# FAT42.net
KiCad netlist of a schematic drawn in Altium Designer
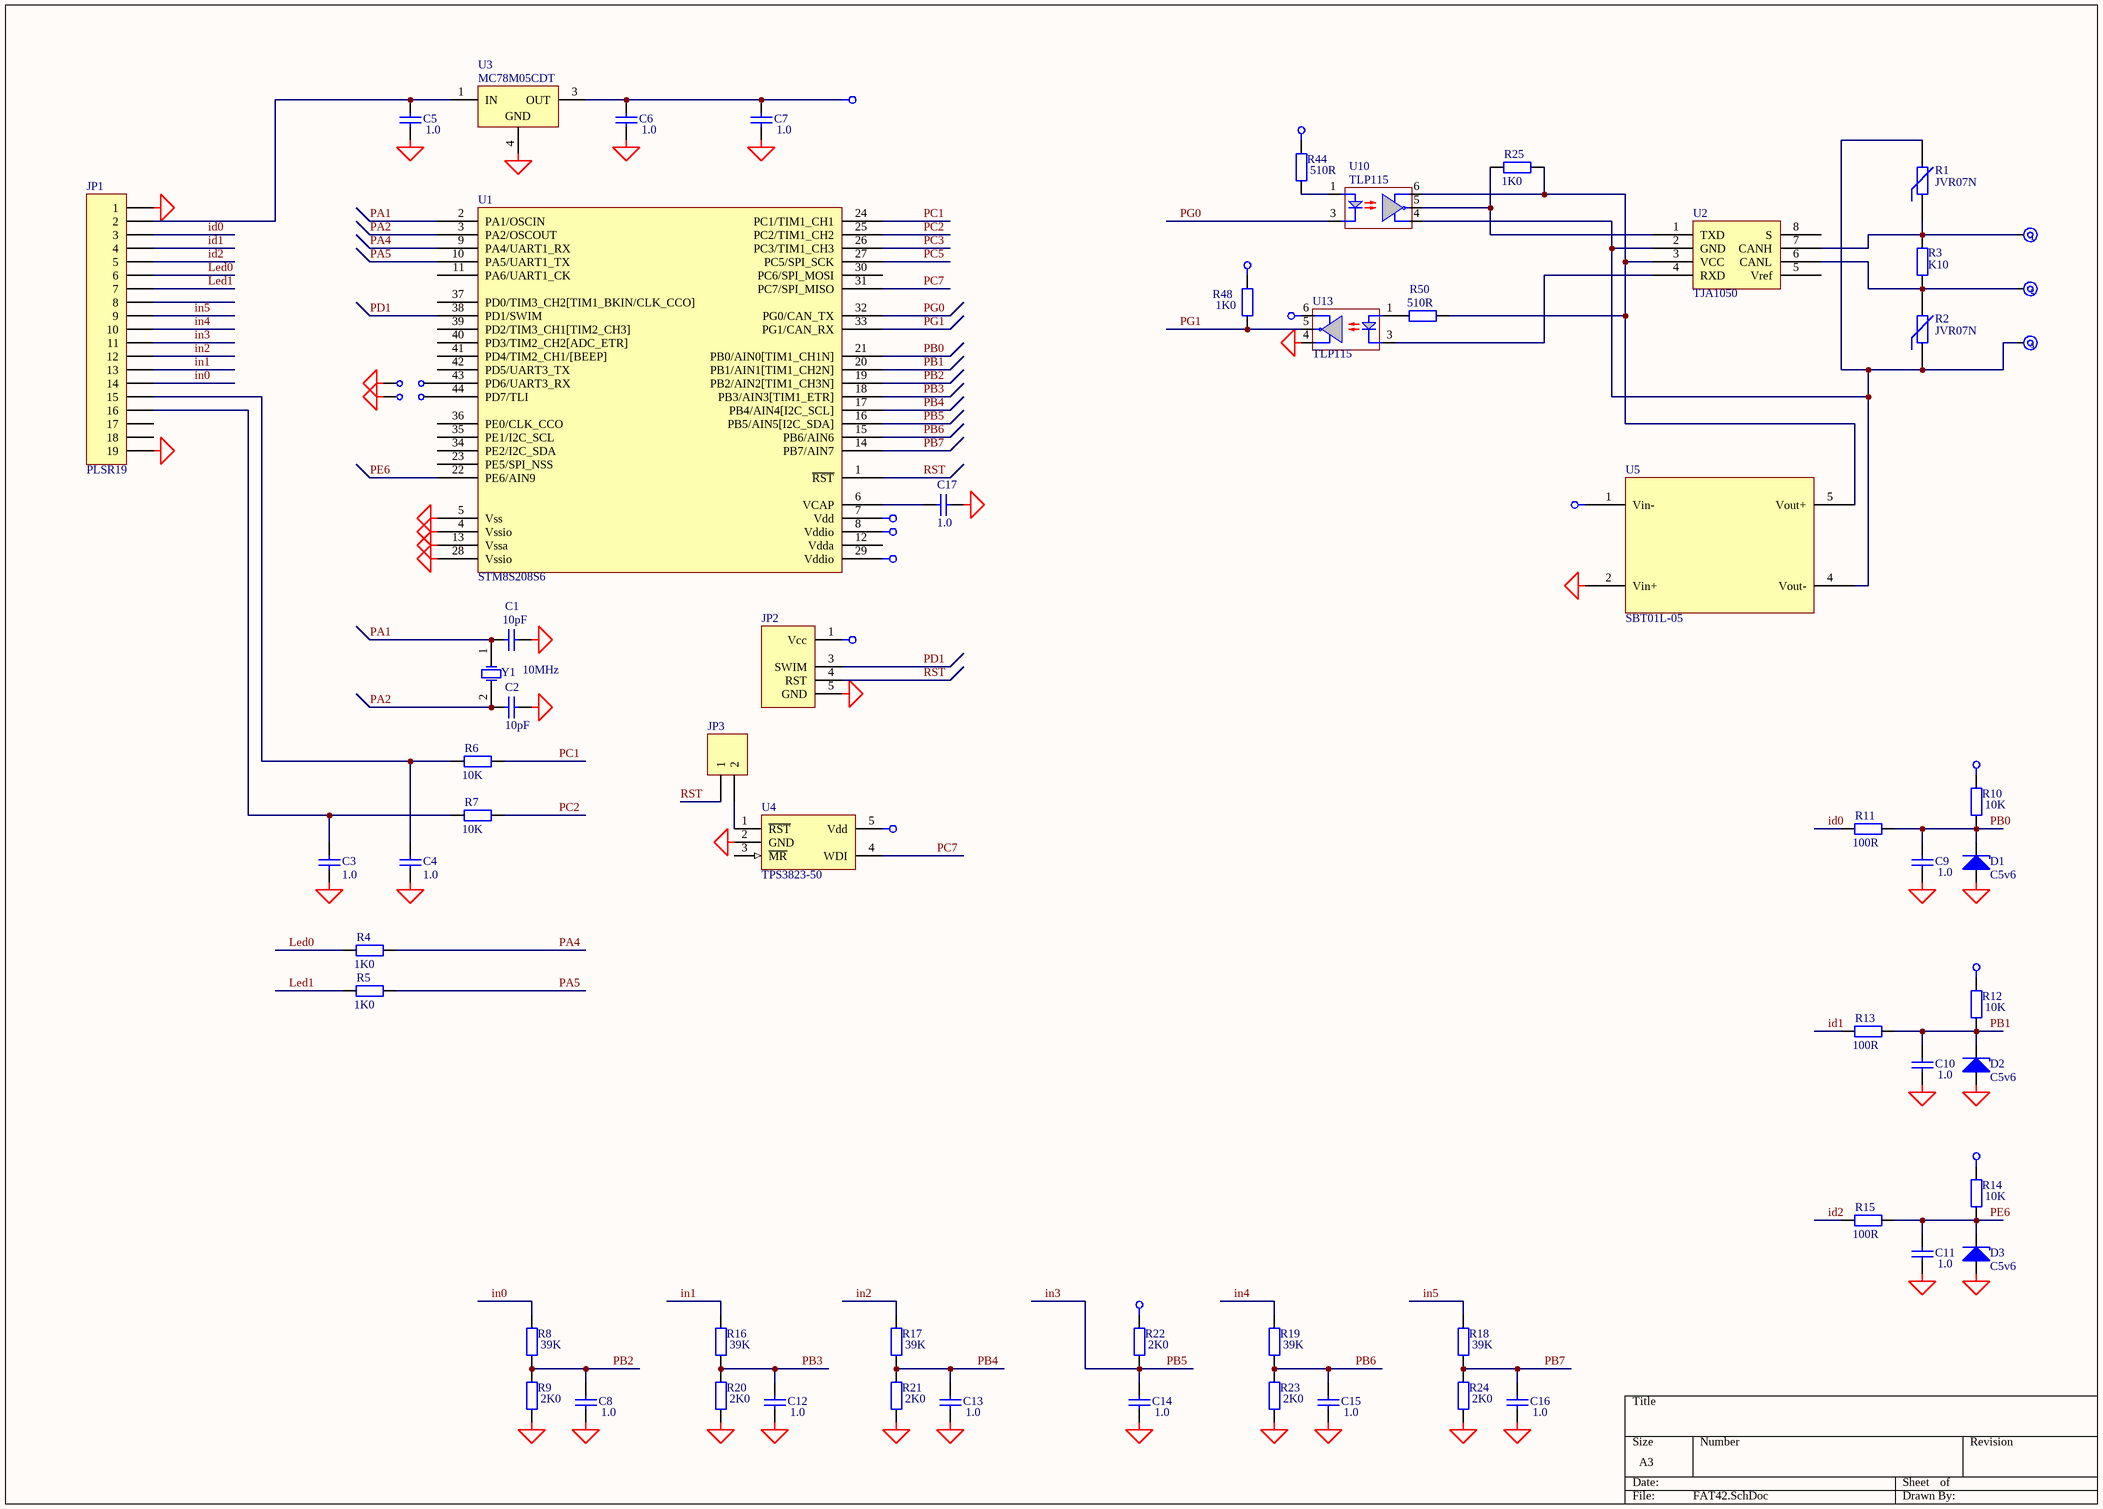
[diagram p0: FAT42.SchDoc]

(export (version "E")
  (design (tool "Eeschema 10.0.6"))
  (components
    (comp (ref "1")
      (value "~")
      (footprint "PIN2R")
      (description "Socket")
      (fields (field (name "MANUFACTURER") "Generic Components") (field (name "PUBLISHER") "Altium Limited"))
      (libsource (lib "PAL") (part "Socket_Ring"))
    )
    (comp (ref "2")
      (value "~")
      (footprint "PIN2R")
      (description "Socket")
      (fields (field (name "MANUFACTURER") "Generic Components") (field (name "PUBLISHER") "Altium Limited"))
      (libsource (lib "PAL") (part "Socket_Ring"))
    )
    (comp (ref "3")
      (value "~")
      (footprint "PIN2R")
      (description "Socket")
      (fields (field (name "MANUFACTURER") "Generic Components") (field (name "PUBLISHER") "Altium Limited"))
      (libsource (lib "PAL") (part "Socket_Ring"))
    )
    (comp (ref "C1")
      (value "10pF")
      (footprint "_1206")
      (description "Capacitor (Semiconductor SIM Model)")
      (fields (field (name "MANUFACTURER") "Generic Components") (field (name "PUBLISHER") "Altium Limited"))
      (libsource (lib "Miscellaneous Devices") (part "Cap Semi"))
    )
    (comp (ref "C2")
      (value "10pF")
      (footprint "_1206")
      (description "Capacitor (Semiconductor SIM Model)")
      (fields (field (name "MANUFACTURER") "Generic Components") (field (name "PUBLISHER") "Altium Limited"))
      (libsource (lib "Miscellaneous Devices") (part "Cap Semi"))
    )
    (comp (ref "C3")
      (value "1.0")
      (footprint "_1206")
      (description "Capacitor (Semiconductor SIM Model)")
      (fields (field (name "MANUFACTURER") "Generic Components") (field (name "PUBLISHER") "Altium Limited"))
      (libsource (lib "Miscellaneous Devices") (part "Cap Semi"))
    )
    (comp (ref "C4")
      (value "1.0")
      (footprint "_1206")
      (description "Capacitor (Semiconductor SIM Model)")
      (fields (field (name "MANUFACTURER") "Generic Components") (field (name "PUBLISHER") "Altium Limited"))
      (libsource (lib "Miscellaneous Devices") (part "Cap Semi"))
    )
    (comp (ref "C5")
      (value "1.0")
      (footprint "_1206")
      (description "Capacitor (Semiconductor SIM Model)")
      (fields (field (name "MANUFACTURER") "Generic Components") (field (name "PUBLISHER") "Altium Limited"))
      (libsource (lib "Miscellaneous Devices") (part "Cap Semi"))
    )
    (comp (ref "C6")
      (value "1.0")
      (footprint "_1206")
      (description "Capacitor (Semiconductor SIM Model)")
      (fields (field (name "MANUFACTURER") "Generic Components") (field (name "PUBLISHER") "Altium Limited"))
      (libsource (lib "Miscellaneous Devices") (part "Cap Semi"))
    )
    (comp (ref "C7")
      (value "1.0")
      (footprint "_1206")
      (description "Capacitor (Semiconductor SIM Model)")
      (fields (field (name "MANUFACTURER") "Generic Components") (field (name "PUBLISHER") "Altium Limited"))
      (libsource (lib "Miscellaneous Devices") (part "Cap Semi"))
    )
    (comp (ref "C8")
      (value "1.0")
      (footprint "_1206")
      (description "Capacitor (Semiconductor SIM Model)")
      (fields (field (name "MANUFACTURER") "Generic Components") (field (name "PUBLISHER") "Altium Limited"))
      (libsource (lib "Miscellaneous Devices") (part "Cap Semi"))
    )
    (comp (ref "C9")
      (value "1.0")
      (footprint "_1206")
      (description "Capacitor (Semiconductor SIM Model)")
      (fields (field (name "MANUFACTURER") "Generic Components") (field (name "PUBLISHER") "Altium Limited"))
      (libsource (lib "Miscellaneous Devices") (part "Cap Semi"))
    )
    (comp (ref "C10")
      (value "1.0")
      (footprint "_1206")
      (description "Capacitor (Semiconductor SIM Model)")
      (fields (field (name "MANUFACTURER") "Generic Components") (field (name "PUBLISHER") "Altium Limited"))
      (libsource (lib "Miscellaneous Devices") (part "Cap Semi"))
    )
    (comp (ref "C11")
      (value "1.0")
      (footprint "_1206")
      (description "Capacitor (Semiconductor SIM Model)")
      (fields (field (name "MANUFACTURER") "Generic Components") (field (name "PUBLISHER") "Altium Limited"))
      (libsource (lib "Miscellaneous Devices") (part "Cap Semi"))
    )
    (comp (ref "C12")
      (value "1.0")
      (footprint "_1206")
      (description "Capacitor (Semiconductor SIM Model)")
      (fields (field (name "MANUFACTURER") "Generic Components") (field (name "PUBLISHER") "Altium Limited"))
      (libsource (lib "Miscellaneous Devices") (part "Cap Semi"))
    )
    (comp (ref "C13")
      (value "1.0")
      (footprint "_1206")
      (description "Capacitor (Semiconductor SIM Model)")
      (fields (field (name "MANUFACTURER") "Generic Components") (field (name "PUBLISHER") "Altium Limited"))
      (libsource (lib "Miscellaneous Devices") (part "Cap Semi"))
    )
    (comp (ref "C14")
      (value "1.0")
      (footprint "_1206")
      (description "Capacitor (Semiconductor SIM Model)")
      (fields (field (name "MANUFACTURER") "Generic Components") (field (name "PUBLISHER") "Altium Limited"))
      (libsource (lib "Miscellaneous Devices") (part "Cap Semi"))
    )
    (comp (ref "C15")
      (value "1.0")
      (footprint "_1206")
      (description "Capacitor (Semiconductor SIM Model)")
      (fields (field (name "MANUFACTURER") "Generic Components") (field (name "PUBLISHER") "Altium Limited"))
      (libsource (lib "Miscellaneous Devices") (part "Cap Semi"))
    )
    (comp (ref "C16")
      (value "1.0")
      (footprint "_1206")
      (description "Capacitor (Semiconductor SIM Model)")
      (fields (field (name "MANUFACTURER") "Generic Components") (field (name "PUBLISHER") "Altium Limited"))
      (libsource (lib "Miscellaneous Devices") (part "Cap Semi"))
    )
    (comp (ref "C17")
      (value "1.0")
      (footprint "_1206")
      (description "Capacitor (Semiconductor SIM Model)")
      (fields (field (name "MANUFACTURER") "Generic Components") (field (name "PUBLISHER") "Altium Limited"))
      (libsource (lib "Miscellaneous Devices") (part "Cap Semi"))
    )
    (comp (ref "D1")
      (value "C5v6")
      (footprint "_1206d")
      (description "Default Diode")
      (fields (field (name "MANUFACTURER") "Generic Components") (field (name "PUBLISHER") "Altium Limited"))
      (libsource (lib "PAL") (part "Zener"))
    )
    (comp (ref "D2")
      (value "C5v6")
      (footprint "_1206d")
      (description "Default Diode")
      (fields (field (name "MANUFACTURER") "Generic Components") (field (name "PUBLISHER") "Altium Limited"))
      (libsource (lib "PAL") (part "Zener"))
    )
    (comp (ref "D3")
      (value "C5v6")
      (footprint "_1206d")
      (description "Default Diode")
      (fields (field (name "MANUFACTURER") "Generic Components") (field (name "PUBLISHER") "Altium Limited"))
      (libsource (lib "PAL") (part "Zener"))
    )
    (comp (ref "J1")
      (value "~")
      (footprint "jmp")
      (description "Switch")
      (fields (field (name "MANUFACTURER") "Generic Components") (field (name "PUBLISHER") "Altium Limited"))
      (libsource (lib "PAL") (part "JMP"))
    )
    (comp (ref "J2")
      (value "~")
      (footprint "jmp")
      (description "Switch")
      (fields (field (name "MANUFACTURER") "Generic Components") (field (name "PUBLISHER") "Altium Limited"))
      (libsource (lib "PAL") (part "JMP"))
    )
    (comp (ref "JP1")
      (value "PLSR19")
      (footprint "HDR1X19")
      (description "Header, 19-Pin")
      (fields (field (name "MANUFACTURER") "Generic Components") (field (name "PUBLISHER") "Altium Limited"))
      (libsource (lib "Miscellaneous Connectors") (part "Header 19"))
    )
    (comp (ref "JP2") (value "~") (footprint "HDR1X5_uart") (libsource (lib "PAL") (part "SWIM_CONN")))
    (comp (ref "JP3")
      (value "PLS2")
      (footprint "HDR1X2")
      (description "Header, 2-Pin")
      (fields (field (name "MANUFACTURER") "Generic Components") (field (name "PUBLISHER") "Altium Limited"))
      (libsource (lib "Miscellaneous Connectors") (part "Header 2"))
    )
    (comp (ref "R1")
      (value "JVR07N")
      (footprint "JVR07N")
      (description "Varistor (Voltage-Sensitive Resistor)")
      (fields (field (name "MANUFACTURER") "Generic Components") (field (name "PUBLISHER") "Altium Limited"))
      (libsource (lib "Miscellaneous Devices") (part "Res Varistor"))
    )
    (comp (ref "R2")
      (value "JVR07N")
      (footprint "JVR07N")
      (description "Varistor (Voltage-Sensitive Resistor)")
      (fields (field (name "MANUFACTURER") "Generic Components") (field (name "PUBLISHER") "Altium Limited"))
      (libsource (lib "Miscellaneous Devices") (part "Res Varistor"))
    )
    (comp (ref "R3")
      (value "K10")
      (footprint "_1206")
      (description "Resistor")
      (fields (field (name "MANUFACTURER") "Generic Components") (field (name "PUBLISHER") "Altium Limited"))
      (libsource (lib "") (part "Res2_5"))
    )
    (comp (ref "R4")
      (value "1K0")
      (footprint "_1206")
      (description "Resistor")
      (fields (field (name "MANUFACTURER") "Generic Components") (field (name "PUBLISHER") "Altium Limited"))
      (libsource (lib "") (part "Res2_5"))
    )
    (comp (ref "R5")
      (value "1K0")
      (footprint "_1206")
      (description "Resistor")
      (fields (field (name "MANUFACTURER") "Generic Components") (field (name "PUBLISHER") "Altium Limited"))
      (libsource (lib "") (part "Res2_5"))
    )
    (comp (ref "R6")
      (value "10K")
      (footprint "_1206")
      (description "Resistor")
      (fields (field (name "MANUFACTURER") "Generic Components") (field (name "PUBLISHER") "Altium Limited"))
      (libsource (lib "") (part "Res2_2"))
    )
    (comp (ref "R7")
      (value "10K")
      (footprint "_1206")
      (description "Resistor")
      (fields (field (name "MANUFACTURER") "Generic Components") (field (name "PUBLISHER") "Altium Limited"))
      (libsource (lib "") (part "Res2_2"))
    )
    (comp (ref "R8")
      (value "39K")
      (footprint "_1206")
      (description "Resistor")
      (fields (field (name "MANUFACTURER") "Generic Components") (field (name "PUBLISHER") "Altium Limited"))
      (libsource (lib "Miscellaneous Devices") (part "Res2"))
    )
    (comp (ref "R9")
      (value "2K0")
      (footprint "_1206")
      (description "Resistor")
      (fields (field (name "MANUFACTURER") "Generic Components") (field (name "PUBLISHER") "Altium Limited"))
      (libsource (lib "Miscellaneous Devices") (part "Res2"))
    )
    (comp (ref "R10")
      (value "10K")
      (footprint "_1206")
      (description "Resistor")
      (fields (field (name "MANUFACTURER") "Generic Components") (field (name "PUBLISHER") "Altium Limited"))
      (libsource (lib "") (part "Res2_3"))
    )
    (comp (ref "R11")
      (value "100R")
      (footprint "_1206")
      (description "Resistor")
      (fields (field (name "MANUFACTURER") "Generic Components") (field (name "PUBLISHER") "Altium Limited"))
      (libsource (lib "") (part "Res2_2"))
    )
    (comp (ref "R12")
      (value "10K")
      (footprint "_1206")
      (description "Resistor")
      (fields (field (name "MANUFACTURER") "Generic Components") (field (name "PUBLISHER") "Altium Limited"))
      (libsource (lib "") (part "Res2_3"))
    )
    (comp (ref "R13")
      (value "100R")
      (footprint "_1206")
      (description "Resistor")
      (fields (field (name "MANUFACTURER") "Generic Components") (field (name "PUBLISHER") "Altium Limited"))
      (libsource (lib "") (part "Res2_2"))
    )
    (comp (ref "R14")
      (value "10K")
      (footprint "_1206")
      (description "Resistor")
      (fields (field (name "MANUFACTURER") "Generic Components") (field (name "PUBLISHER") "Altium Limited"))
      (libsource (lib "") (part "Res2_3"))
    )
    (comp (ref "R15")
      (value "100R")
      (footprint "_1206")
      (description "Resistor")
      (fields (field (name "MANUFACTURER") "Generic Components") (field (name "PUBLISHER") "Altium Limited"))
      (libsource (lib "") (part "Res2_2"))
    )
    (comp (ref "R16")
      (value "39K")
      (footprint "_1206")
      (description "Resistor")
      (fields (field (name "MANUFACTURER") "Generic Components") (field (name "PUBLISHER") "Altium Limited"))
      (libsource (lib "Miscellaneous Devices") (part "Res2"))
    )
    (comp (ref "R17")
      (value "39K")
      (footprint "_1206")
      (description "Resistor")
      (fields (field (name "MANUFACTURER") "Generic Components") (field (name "PUBLISHER") "Altium Limited"))
      (libsource (lib "Miscellaneous Devices") (part "Res2"))
    )
    (comp (ref "R18")
      (value "39K")
      (footprint "_1206")
      (description "Resistor")
      (fields (field (name "MANUFACTURER") "Generic Components") (field (name "PUBLISHER") "Altium Limited"))
      (libsource (lib "Miscellaneous Devices") (part "Res2"))
    )
    (comp (ref "R19")
      (value "39K")
      (footprint "_1206")
      (description "Resistor")
      (fields (field (name "MANUFACTURER") "Generic Components") (field (name "PUBLISHER") "Altium Limited"))
      (libsource (lib "Miscellaneous Devices") (part "Res2"))
    )
    (comp (ref "R20")
      (value "2K0")
      (footprint "_1206")
      (description "Resistor")
      (fields (field (name "MANUFACTURER") "Generic Components") (field (name "PUBLISHER") "Altium Limited"))
      (libsource (lib "Miscellaneous Devices") (part "Res2"))
    )
    (comp (ref "R21")
      (value "2K0")
      (footprint "_1206")
      (description "Resistor")
      (fields (field (name "MANUFACTURER") "Generic Components") (field (name "PUBLISHER") "Altium Limited"))
      (libsource (lib "Miscellaneous Devices") (part "Res2"))
    )
    (comp (ref "R22")
      (value "2K0")
      (footprint "_1206")
      (description "Resistor")
      (fields (field (name "MANUFACTURER") "Generic Components") (field (name "PUBLISHER") "Altium Limited"))
      (libsource (lib "Miscellaneous Devices") (part "Res2"))
    )
    (comp (ref "R23")
      (value "2K0")
      (footprint "_1206")
      (description "Resistor")
      (fields (field (name "MANUFACTURER") "Generic Components") (field (name "PUBLISHER") "Altium Limited"))
      (libsource (lib "Miscellaneous Devices") (part "Res2"))
    )
    (comp (ref "R24")
      (value "2K0")
      (footprint "_1206")
      (description "Resistor")
      (fields (field (name "MANUFACTURER") "Generic Components") (field (name "PUBLISHER") "Altium Limited"))
      (libsource (lib "Miscellaneous Devices") (part "Res2"))
    )
    (comp (ref "R25")
      (value "1K0")
      (footprint "_1206")
      (description "Resistor")
      (fields (field (name "MANUFACTURER") "Generic Components") (field (name "PUBLISHER") "Altium Limited"))
      (libsource (lib "") (part "Res2_1"))
    )
    (comp (ref "R44")
      (value "510R")
      (footprint "_1206")
      (description "Resistor")
      (fields (field (name "MANUFACTURER") "Generic Components") (field (name "PUBLISHER") "Altium Limited"))
      (libsource (lib "") (part "Res2_5"))
    )
    (comp (ref "R48")
      (value "1K0")
      (footprint "_1206")
      (description "Resistor")
      (fields (field (name "MANUFACTURER") "Generic Components") (field (name "PUBLISHER") "Altium Limited"))
      (libsource (lib "") (part "Res2_5"))
    )
    (comp (ref "R50")
      (value "510R")
      (footprint "_1206")
      (description "Resistor")
      (fields (field (name "MANUFACTURER") "Generic Components") (field (name "PUBLISHER") "Altium Limited"))
      (libsource (lib "") (part "Res2_4"))
    )
    (comp (ref "U1")
      (value "STM8S208S6")
      (footprint "QFP10X10-G44/G10N")
      (libsource (lib "PAL") (part "STM8S208S6"))
    )
    (comp (ref "U2") (value "TJA1050") (footprint "SO-G8/D5") (libsource (lib "PAL") (part "TJA1050")))
    (comp (ref "U3")
      (value "MC78M05CDT")
      (footprint "SIP-G3/Z11.05")
      (description "Three-Terminal Medium Current Positive Voltage Regulator")
      (fields (field (name "MANUFACTURER") "ON Semiconductor") (field (name "PUBLISHER") "Altium Limited"))
      (libsource (lib "ON Semi Power Mgt Voltage Regulator") (part "MC78M05CDT"))
    )
    (comp (ref "U4")
      (value "TPS3823-50")
      (footprint "SO-G5/P.95")
      (description "Reset IC")
      (fields
        (field (name "MANUFACTURER") "National Semiconductor")
        (field (name "PUBLISHER") "Altium Limited")
      )
      (libsource (lib "PAL") (part "TPS3823"))
    )
    (comp (ref "U5") (value "SBT01L-05") (footprint "SBT01DET01") (libsource (lib "PAL") (part "SBT01L")))
    (comp (ref "U10") (value "TLP115") (footprint "tlp115") (libsource (lib "PAL") (part "TLP115")))
    (comp (ref "U13") (value "TLP115") (footprint "tlp115") (libsource (lib "") (part "TLP115_1")))
    (comp (ref "Y1")
      (value "10MHz")
      (footprint "QWARZ1")
      (description "Crystal Oscillator")
      (fields (field (name "MANUFACTURER") "Generic Components") (field (name "PUBLISHER") "Altium Limited"))
      (libsource (lib "Miscellaneous Devices") (part "XTAL"))
    )
  )
  (nets
    (net (code "1") (name "+5v") (class "Default")
      (node (ref "C6") (pin "2") (pinfunction "2_2") (pintype "passive"))
      (node (ref "C7") (pin "2") (pinfunction "2_2") (pintype "passive"))
      (node (ref "JP2") (pin "1") (pinfunction "Vcc_1") (pintype "passive"))
      (node (ref "R10") (pin "1") (pinfunction "1_1") (pintype "passive"))
      (node (ref "R12") (pin "1") (pinfunction "1_1") (pintype "passive"))
      (node (ref "R14") (pin "1") (pinfunction "1_1") (pintype "passive"))
      (node (ref "R22") (pin "2") (pinfunction "2_2") (pintype "passive"))
      (node (ref "R44") (pin "2") (pinfunction "2_2") (pintype "passive"))
      (node (ref "R48") (pin "2") (pinfunction "2_2") (pintype "passive"))
      (node (ref "U1") (pin "29") (pinfunction "Vddio_29") (pintype "passive"))
      (node (ref "U1") (pin "7") (pinfunction "Vdd_7") (pintype "passive"))
      (node (ref "U1") (pin "8") (pinfunction "Vddio_8") (pintype "passive"))
      (node (ref "U13") (pin "6") (pinfunction "6_6") (pintype "passive"))
      (node (ref "U3") (pin "3") (pinfunction "OUT_3") (pintype "power_in"))
      (node (ref "U4") (pin "5") (pinfunction "Vdd_5") (pintype "power_in"))
      (node (ref "U5") (pin "1") (pinfunction "Vin-_1") (pintype "passive"))
    )
    (net (code "2") (name "/Led0") (class "Default")
      (node (ref "JP1") (pin "6") (pinfunction "6_6") (pintype "passive"))
      (node (ref "R4") (pin "1") (pinfunction "1_1") (pintype "passive"))
    )
    (net (code "3") (name "/Led1") (class "Default")
      (node (ref "JP1") (pin "7") (pinfunction "7_7") (pintype "passive"))
      (node (ref "R5") (pin "1") (pinfunction "1_1") (pintype "passive"))
    )
    (net (code "4") (name "/PA1") (class "Default")
      (node (ref "C1") (pin "2") (pinfunction "2_2") (pintype "passive"))
      (node (ref "U1") (pin "2") (pinfunction "PA1/OSCIN_2") (pintype "passive"))
      (node (ref "Y1") (pin "1") (pinfunction "OSC1_1") (pintype "passive"))
    )
    (net (code "5") (name "/PA2") (class "Default")
      (node (ref "C2") (pin "2") (pinfunction "2_2") (pintype "passive"))
      (node (ref "U1") (pin "3") (pinfunction "PA2/OSCOUT_3") (pintype "passive"))
      (node (ref "Y1") (pin "2") (pinfunction "OSC2_2") (pintype "passive"))
    )
    (net (code "6") (name "/PA4") (class "Default")
      (node (ref "R4") (pin "2") (pinfunction "2_2") (pintype "passive"))
      (node (ref "U1") (pin "9") (pinfunction "PA4/UART1_RX_9") (pintype "passive"))
    )
    (net (code "7") (name "/PA5") (class "Default")
      (node (ref "R5") (pin "2") (pinfunction "2_2") (pintype "passive"))
      (node (ref "U1") (pin "10") (pinfunction "PA5/UART1_TX_10") (pintype "passive"))
    )
    (net (code "8") (name "/PB0") (class "Default")
      (node (ref "C9") (pin "2") (pinfunction "2_2") (pintype "passive"))
      (node (ref "D1") (pin "2") (pinfunction "K_2") (pintype "passive"))
      (node (ref "R10") (pin "2") (pinfunction "2_2") (pintype "passive"))
      (node (ref "R11") (pin "1") (pinfunction "1_1") (pintype "passive"))
      (node (ref "U1") (pin "21") (pinfunction "PB0/AIN0[TIM1_CH1N]_21") (pintype "passive"))
    )
    (net (code "9") (name "/PB1") (class "Default")
      (node (ref "C10") (pin "2") (pinfunction "2_2") (pintype "passive"))
      (node (ref "D2") (pin "2") (pinfunction "K_2") (pintype "passive"))
      (node (ref "R12") (pin "2") (pinfunction "2_2") (pintype "passive"))
      (node (ref "R13") (pin "1") (pinfunction "1_1") (pintype "passive"))
      (node (ref "U1") (pin "20") (pinfunction "PB1/AIN1[TIM1_CH2N]_20") (pintype "passive"))
    )
    (net (code "10") (name "/PB2") (class "Default")
      (node (ref "C8") (pin "2") (pinfunction "2_2") (pintype "passive"))
      (node (ref "R8") (pin "1") (pinfunction "1_1") (pintype "passive"))
      (node (ref "R9") (pin "2") (pinfunction "2_2") (pintype "passive"))
      (node (ref "U1") (pin "19") (pinfunction "PB2/AIN2[TIM1_CH3N]_19") (pintype "passive"))
    )
    (net (code "11") (name "/PB3") (class "Default")
      (node (ref "C12") (pin "2") (pinfunction "2_2") (pintype "passive"))
      (node (ref "R16") (pin "1") (pinfunction "1_1") (pintype "passive"))
      (node (ref "R20") (pin "2") (pinfunction "2_2") (pintype "passive"))
      (node (ref "U1") (pin "18") (pinfunction "PB3/AIN3[TIM1_ETR]_18") (pintype "passive"))
    )
    (net (code "12") (name "/PB4") (class "Default")
      (node (ref "C13") (pin "2") (pinfunction "2_2") (pintype "passive"))
      (node (ref "R17") (pin "1") (pinfunction "1_1") (pintype "passive"))
      (node (ref "R21") (pin "2") (pinfunction "2_2") (pintype "passive"))
      (node (ref "U1") (pin "17") (pinfunction "PB4/AIN4[I2C_SCL]_17") (pintype "passive"))
    )
    (net (code "13") (name "/PB5") (class "Default")
      (node (ref "C14") (pin "2") (pinfunction "2_2") (pintype "passive"))
      (node (ref "JP1") (pin "11") (pinfunction "11_11") (pintype "passive"))
      (node (ref "R22") (pin "1") (pinfunction "1_1") (pintype "passive"))
      (node (ref "U1") (pin "16") (pinfunction "PB5/AIN5[I2C_SDA]_16") (pintype "passive"))
    )
    (net (code "14") (name "/PB6") (class "Default")
      (node (ref "C15") (pin "2") (pinfunction "2_2") (pintype "passive"))
      (node (ref "R19") (pin "1") (pinfunction "1_1") (pintype "passive"))
      (node (ref "R23") (pin "2") (pinfunction "2_2") (pintype "passive"))
      (node (ref "U1") (pin "15") (pinfunction "PB6/AIN6_15") (pintype "passive"))
    )
    (net (code "15") (name "/PB7") (class "Default")
      (node (ref "C16") (pin "2") (pinfunction "2_2") (pintype "passive"))
      (node (ref "R18") (pin "1") (pinfunction "1_1") (pintype "passive"))
      (node (ref "R24") (pin "2") (pinfunction "2_2") (pintype "passive"))
      (node (ref "U1") (pin "14") (pinfunction "PB7/AIN7_14") (pintype "passive"))
    )
    (net (code "16") (name "/PC1") (class "Default")
      (node (ref "R6") (pin "1") (pinfunction "1_1") (pintype "passive"))
      (node (ref "U1") (pin "24") (pinfunction "PC1/TIM1_CH1_24") (pintype "passive"))
    )
    (net (code "17") (name "/PC2") (class "Default")
      (node (ref "R7") (pin "1") (pinfunction "1_1") (pintype "passive"))
      (node (ref "U1") (pin "25") (pinfunction "PC2/TIM1_CH2_25") (pintype "passive"))
    )
    (net (code "18") (name "/PC3") (class "Default")
      (node (ref "U1") (pin "26") (pinfunction "PC3/TIM1_CH3_26") (pintype "passive"))
    )
    (net (code "19") (name "/PC5") (class "Default")
      (node (ref "U1") (pin "27") (pinfunction "PC5/SPI_SCK_27") (pintype "passive"))
    )
    (net (code "20") (name "/PC7") (class "Default")
      (node (ref "U1") (pin "31") (pinfunction "PC7/SPI_MISO_31") (pintype "passive"))
      (node (ref "U4") (pin "4") (pinfunction "WDI_4") (pintype "passive"))
    )
    (net (code "21") (name "/PD1") (class "Default")
      (node (ref "JP2") (pin "3") (pinfunction "SWIM_3") (pintype "passive"))
      (node (ref "U1") (pin "38") (pinfunction "PD1/SWIM_38") (pintype "passive"))
    )
    (net (code "22") (name "/PE6") (class "Default")
      (node (ref "C11") (pin "2") (pinfunction "2_2") (pintype "passive"))
      (node (ref "D3") (pin "2") (pinfunction "K_2") (pintype "passive"))
      (node (ref "R14") (pin "2") (pinfunction "2_2") (pintype "passive"))
      (node (ref "R15") (pin "1") (pinfunction "1_1") (pintype "passive"))
      (node (ref "U1") (pin "22") (pinfunction "PE6/AIN9_22") (pintype "passive"))
    )
    (net (code "23") (name "/PG0") (class "Default")
      (node (ref "U1") (pin "32") (pinfunction "PG0/CAN_TX_32") (pintype "passive"))
      (node (ref "U10") (pin "3") (pinfunction "3_3") (pintype "passive"))
    )
    (net (code "24") (name "/PG1") (class "Default")
      (node (ref "R48") (pin "1") (pinfunction "1_1") (pintype "passive"))
      (node (ref "U1") (pin "33") (pinfunction "PG1/CAN_RX_33") (pintype "passive"))
      (node (ref "U13") (pin "5") (pinfunction "5_5") (pintype "passive"))
    )
    (net (code "25") (name "/RST") (class "Default")
      (node (ref "JP2") (pin "4") (pinfunction "RST_4") (pintype "passive"))
      (node (ref "JP3") (pin "1") (pinfunction "1_1") (pintype "passive"))
      (node (ref "U1") (pin "1") (pinfunction "~{RST}_1") (pintype "passive"))
    )
    (net (code "26") (name "/id0") (class "Default")
      (node (ref "JP1") (pin "3") (pinfunction "3_3") (pintype "passive"))
      (node (ref "R11") (pin "2") (pinfunction "2_2") (pintype "passive"))
    )
    (net (code "27") (name "/id1") (class "Default")
      (node (ref "JP1") (pin "4") (pinfunction "4_4") (pintype "passive"))
      (node (ref "R13") (pin "2") (pinfunction "2_2") (pintype "passive"))
    )
    (net (code "28") (name "/id2") (class "Default")
      (node (ref "JP1") (pin "5") (pinfunction "5_5") (pintype "passive"))
      (node (ref "R15") (pin "2") (pinfunction "2_2") (pintype "passive"))
    )
    (net (code "29") (name "/in0") (class "Default")
      (node (ref "JP1") (pin "14") (pinfunction "14_14") (pintype "passive"))
      (node (ref "R8") (pin "2") (pinfunction "2_2") (pintype "passive"))
    )
    (net (code "30") (name "/in1") (class "Default")
      (node (ref "JP1") (pin "13") (pinfunction "13_13") (pintype "passive"))
      (node (ref "R16") (pin "2") (pinfunction "2_2") (pintype "passive"))
    )
    (net (code "31") (name "/in2") (class "Default")
      (node (ref "JP1") (pin "12") (pinfunction "12_12") (pintype "passive"))
      (node (ref "R17") (pin "2") (pinfunction "2_2") (pintype "passive"))
    )
    (net (code "32") (name "/in4") (class "Default")
      (node (ref "JP1") (pin "10") (pinfunction "10_10") (pintype "passive"))
      (node (ref "R19") (pin "2") (pinfunction "2_2") (pintype "passive"))
    )
    (net (code "33") (name "/in5") (class "Default")
      (node (ref "JP1") (pin "9") (pinfunction "9_9") (pintype "passive"))
      (node (ref "R18") (pin "2") (pinfunction "2_2") (pintype "passive"))
    )
    (net (code "34") (name "GND") (class "Default")
      (node (ref "C1") (pin "1") (pinfunction "1_1") (pintype "passive"))
      (node (ref "C10") (pin "1") (pinfunction "1_1") (pintype "passive"))
      (node (ref "C11") (pin "1") (pinfunction "1_1") (pintype "passive"))
      (node (ref "C12") (pin "1") (pinfunction "1_1") (pintype "passive"))
      (node (ref "C13") (pin "1") (pinfunction "1_1") (pintype "passive"))
      (node (ref "C14") (pin "1") (pinfunction "1_1") (pintype "passive"))
      (node (ref "C15") (pin "1") (pinfunction "1_1") (pintype "passive"))
      (node (ref "C16") (pin "1") (pinfunction "1_1") (pintype "passive"))
      (node (ref "C17") (pin "1") (pinfunction "1_1") (pintype "passive"))
      (node (ref "C2") (pin "1") (pinfunction "1_1") (pintype "passive"))
      (node (ref "C3") (pin "1") (pinfunction "1_1") (pintype "passive"))
      (node (ref "C4") (pin "1") (pinfunction "1_1") (pintype "passive"))
      (node (ref "C5") (pin "1") (pinfunction "1_1") (pintype "passive"))
      (node (ref "C6") (pin "1") (pinfunction "1_1") (pintype "passive"))
      (node (ref "C7") (pin "1") (pinfunction "1_1") (pintype "passive"))
      (node (ref "C8") (pin "1") (pinfunction "1_1") (pintype "passive"))
      (node (ref "C9") (pin "1") (pinfunction "1_1") (pintype "passive"))
      (node (ref "D1") (pin "1") (pinfunction "A_1") (pintype "passive"))
      (node (ref "D2") (pin "1") (pinfunction "A_1") (pintype "passive"))
      (node (ref "D3") (pin "1") (pinfunction "A_1") (pintype "passive"))
      (node (ref "J1") (pin "1") (pinfunction "1_1") (pintype "passive"))
      (node (ref "J2") (pin "1") (pinfunction "1_1") (pintype "passive"))
      (node (ref "JP1") (pin "1") (pinfunction "1_1") (pintype "passive"))
      (node (ref "JP1") (pin "19") (pinfunction "19_19") (pintype "passive"))
      (node (ref "JP2") (pin "5") (pinfunction "GND_5") (pintype "passive"))
      (node (ref "R20") (pin "1") (pinfunction "1_1") (pintype "passive"))
      (node (ref "R21") (pin "1") (pinfunction "1_1") (pintype "passive"))
      (node (ref "R23") (pin "1") (pinfunction "1_1") (pintype "passive"))
      (node (ref "R24") (pin "1") (pinfunction "1_1") (pintype "passive"))
      (node (ref "R9") (pin "1") (pinfunction "1_1") (pintype "passive"))
      (node (ref "U1") (pin "13") (pinfunction "Vssa_13") (pintype "passive"))
      (node (ref "U1") (pin "28") (pinfunction "Vssio_28") (pintype "passive"))
      (node (ref "U1") (pin "4") (pinfunction "Vssio_4") (pintype "passive"))
      (node (ref "U1") (pin "5") (pinfunction "Vss_5") (pintype "passive"))
      (node (ref "U13") (pin "4") (pinfunction "4_4") (pintype "passive"))
      (node (ref "U3") (pin "4") (pinfunction "GND_4") (pintype "power_in"))
      (node (ref "U4") (pin "2") (pinfunction "GND_2") (pintype "power_in"))
      (node (ref "U5") (pin "2") (pinfunction "Vin+_2") (pintype "passive"))
    )
    (net (code "35") (name "Net-(C3-Pad2)") (class "Default")
      (node (ref "C3") (pin "2") (pinfunction "2_2") (pintype "passive"))
      (node (ref "JP1") (pin "16") (pinfunction "16_16") (pintype "passive"))
      (node (ref "R7") (pin "2") (pinfunction "2_2") (pintype "passive"))
    )
    (net (code "36") (name "Net-(C4-Pad2)") (class "Default")
      (node (ref "C4") (pin "2") (pinfunction "2_2") (pintype "passive"))
      (node (ref "JP1") (pin "15") (pinfunction "15_15") (pintype "passive"))
      (node (ref "R6") (pin "2") (pinfunction "2_2") (pintype "passive"))
    )
    (net (code "37") (name "Net-(R44-Pad1)") (class "Default")
      (node (ref "R44") (pin "1") (pinfunction "1_1") (pintype "passive"))
      (node (ref "U10") (pin "1") (pinfunction "1_1") (pintype "passive"))
    )
    (net (code "38") (name "Net-(R50-Pad2)") (class "Default")
      (node (ref "R50") (pin "2") (pinfunction "2_2") (pintype "passive"))
      (node (ref "U13") (pin "1") (pinfunction "1_1") (pintype "passive"))
    )
    (net (code "39") (name "Net-(U1-PD6{slash}UART3_RX)") (class "Default")
      (node (ref "J1") (pin "2") (pinfunction "2_2") (pintype "passive"))
      (node (ref "U1") (pin "43") (pinfunction "PD6/UART3_RX_43") (pintype "passive"))
    )
    (net (code "40") (name "Net-(U1-PD7{slash}TLI)") (class "Default")
      (node (ref "J2") (pin "2") (pinfunction "2_2") (pintype "passive"))
      (node (ref "U1") (pin "44") (pinfunction "PD7/TLI_44") (pintype "passive"))
    )
    (net (code "41") (name "Net-(U1-VCAP)") (class "Default")
      (node (ref "C17") (pin "2") (pinfunction "2_2") (pintype "passive"))
      (node (ref "U1") (pin "6") (pinfunction "VCAP_6") (pintype "passive"))
    )
    (net (code "42") (name "Net-(U2-CANH)") (class "Default")
      (node (ref "1") (pin "1") (pinfunction "1_1") (pintype "passive"))
      (node (ref "R1") (pin "1") (pinfunction "1_1") (pintype "passive"))
      (node (ref "R3") (pin "2") (pinfunction "2_2") (pintype "passive"))
      (node (ref "U2") (pin "7") (pinfunction "CANH_7") (pintype "passive"))
    )
    (net (code "43") (name "Net-(U2-CANL)") (class "Default")
      (node (ref "2") (pin "1") (pinfunction "1_1") (pintype "passive"))
      (node (ref "R2") (pin "2") (pinfunction "2_2") (pintype "passive"))
      (node (ref "R3") (pin "1") (pinfunction "1_1") (pintype "passive"))
      (node (ref "U2") (pin "6") (pinfunction "CANL_6") (pintype "passive"))
    )
    (net (code "44") (name "Net-(U2-GND)") (class "Default")
      (node (ref "3") (pin "1") (pinfunction "1_1") (pintype "passive"))
      (node (ref "R1") (pin "2") (pinfunction "2_2") (pintype "passive"))
      (node (ref "R2") (pin "1") (pinfunction "1_1") (pintype "passive"))
      (node (ref "U10") (pin "4") (pinfunction "4_4") (pintype "passive"))
      (node (ref "U2") (pin "2") (pinfunction "GND_2") (pintype "passive"))
      (node (ref "U5") (pin "4") (pinfunction "Vout-_4") (pintype "passive"))
    )
    (net (code "45") (name "Net-(U2-RXD)") (class "Default")
      (node (ref "U13") (pin "3") (pinfunction "3_3") (pintype "passive"))
      (node (ref "U2") (pin "4") (pinfunction "RXD_4") (pintype "passive"))
    )
    (net (code "46") (name "Net-(U2-TXD)") (class "Default")
      (node (ref "R25") (pin "1") (pinfunction "1_1") (pintype "passive"))
      (node (ref "U10") (pin "5") (pinfunction "5_5") (pintype "passive"))
      (node (ref "U2") (pin "1") (pinfunction "TXD_1") (pintype "passive"))
    )
    (net (code "47") (name "Net-(U2-VCC)") (class "Default")
      (node (ref "R25") (pin "2") (pinfunction "2_2") (pintype "passive"))
      (node (ref "R50") (pin "1") (pinfunction "1_1") (pintype "passive"))
      (node (ref "U10") (pin "6") (pinfunction "6_6") (pintype "passive"))
      (node (ref "U2") (pin "3") (pinfunction "VCC_3") (pintype "passive"))
      (node (ref "U5") (pin "5") (pinfunction "Vout+_5") (pintype "passive"))
    )
    (net (code "48") (name "Net-(U3-IN)") (class "Default")
      (node (ref "C5") (pin "2") (pinfunction "2_2") (pintype "passive"))
      (node (ref "JP1") (pin "2") (pinfunction "2_2") (pintype "passive"))
      (node (ref "U3") (pin "1") (pinfunction "IN_1") (pintype "power_in"))
    )
    (net (code "49") (name "Net-(U4-~{RST})") (class "Default")
      (node (ref "JP3") (pin "2") (pinfunction "2_2") (pintype "passive"))
      (node (ref "U4") (pin "1") (pinfunction "~{RST}_1") (pintype "power_in"))
    )
    (net (code "50") (name "unconnected-(JP1-Pad8)") (class "Default")
      (node (ref "JP1") (pin "8") (pinfunction "8_8") (pintype "passive"))
    )
    (net (code "51") (name "unconnected-(JP1-Pad17)") (class "Default")
      (node (ref "JP1") (pin "17") (pinfunction "17_17") (pintype "passive"))
    )
    (net (code "52") (name "unconnected-(JP1-Pad18)") (class "Default")
      (node (ref "JP1") (pin "18") (pinfunction "18_18") (pintype "passive"))
    )
    (net (code "53") (name "unconnected-(U1-PA6{slash}UART1_CK-Pad11)") (class "Default")
      (node (ref "U1") (pin "11") (pinfunction "PA6/UART1_CK_11") (pintype "passive"))
    )
    (net (code "54") (name "unconnected-(U1-PC6{slash}SPI_MOSI-Pad30)") (class "Default")
      (node (ref "U1") (pin "30") (pinfunction "PC6/SPI_MOSI_30") (pintype "passive"))
    )
    (net (code "55") (name "unconnected-(U1-PD0{slash}TIM3_CH2[TIM1_BKIN{slash}CLK_CCO]-Pad37)") (class "Default")
      (node (ref "U1") (pin "37") (pinfunction "PD0/TIM3_CH2[TIM1_BKIN/CLK_CCO]_37") (pintype "passive"))
    )
    (net (code "56") (name "unconnected-(U1-PD2{slash}TIM3_CH1[TIM2_CH3]-Pad39)") (class "Default")
      (node (ref "U1") (pin "39") (pinfunction "PD2/TIM3_CH1[TIM2_CH3]_39") (pintype "passive"))
    )
    (net (code "57") (name "unconnected-(U1-PD3{slash}TIM2_CH2[ADC_ETR]-Pad40)") (class "Default")
      (node (ref "U1") (pin "40") (pinfunction "PD3/TIM2_CH2[ADC_ETR]_40") (pintype "passive"))
    )
    (net (code "58") (name "unconnected-(U1-PD4{slash}TIM2_CH1{slash}[BEEP]-Pad41)") (class "Default")
      (node (ref "U1") (pin "41") (pinfunction "PD4/TIM2_CH1/[BEEP]_41") (pintype "passive"))
    )
    (net (code "59") (name "unconnected-(U1-PD5{slash}UART3_TX-Pad42)") (class "Default")
      (node (ref "U1") (pin "42") (pinfunction "PD5/UART3_TX_42") (pintype "passive"))
    )
    (net (code "60") (name "unconnected-(U1-PE0{slash}CLK_CCO-Pad36)") (class "Default")
      (node (ref "U1") (pin "36") (pinfunction "PE0/CLK_CCO_36") (pintype "passive"))
    )
    (net (code "61") (name "unconnected-(U1-PE1{slash}I2C_SCL-Pad35)") (class "Default")
      (node (ref "U1") (pin "35") (pinfunction "PE1/I2C_SCL_35") (pintype "passive"))
    )
    (net (code "62") (name "unconnected-(U1-PE2{slash}I2C_SDA-Pad34)") (class "Default")
      (node (ref "U1") (pin "34") (pinfunction "PE2/I2C_SDA_34") (pintype "passive"))
    )
    (net (code "63") (name "unconnected-(U1-PE5{slash}SPI_NSS-Pad23)") (class "Default")
      (node (ref "U1") (pin "23") (pinfunction "PE5/SPI_NSS_23") (pintype "passive"))
    )
    (net (code "64") (name "unconnected-(U1-Vdda-Pad12)") (class "Default")
      (node (ref "U1") (pin "12") (pinfunction "Vdda_12") (pintype "passive"))
    )
    (net (code "65") (name "unconnected-(U2-S-Pad8)") (class "Default")
      (node (ref "U2") (pin "8") (pinfunction "S_8") (pintype "passive"))
    )
    (net (code "66") (name "unconnected-(U2-Vref-Pad5)") (class "Default")
      (node (ref "U2") (pin "5") (pinfunction "Vref_5") (pintype "passive"))
    )
    (net (code "67") (name "unconnected-(U4-~{MR}-Pad3)") (class "Default")
      (node (ref "U4") (pin "3") (pinfunction "~{MR}_3") (pintype "input"))
    )
  )
)
